# oa_sevenfortyfun.net
KiCad netlist of a schematic drawn in EAGLE
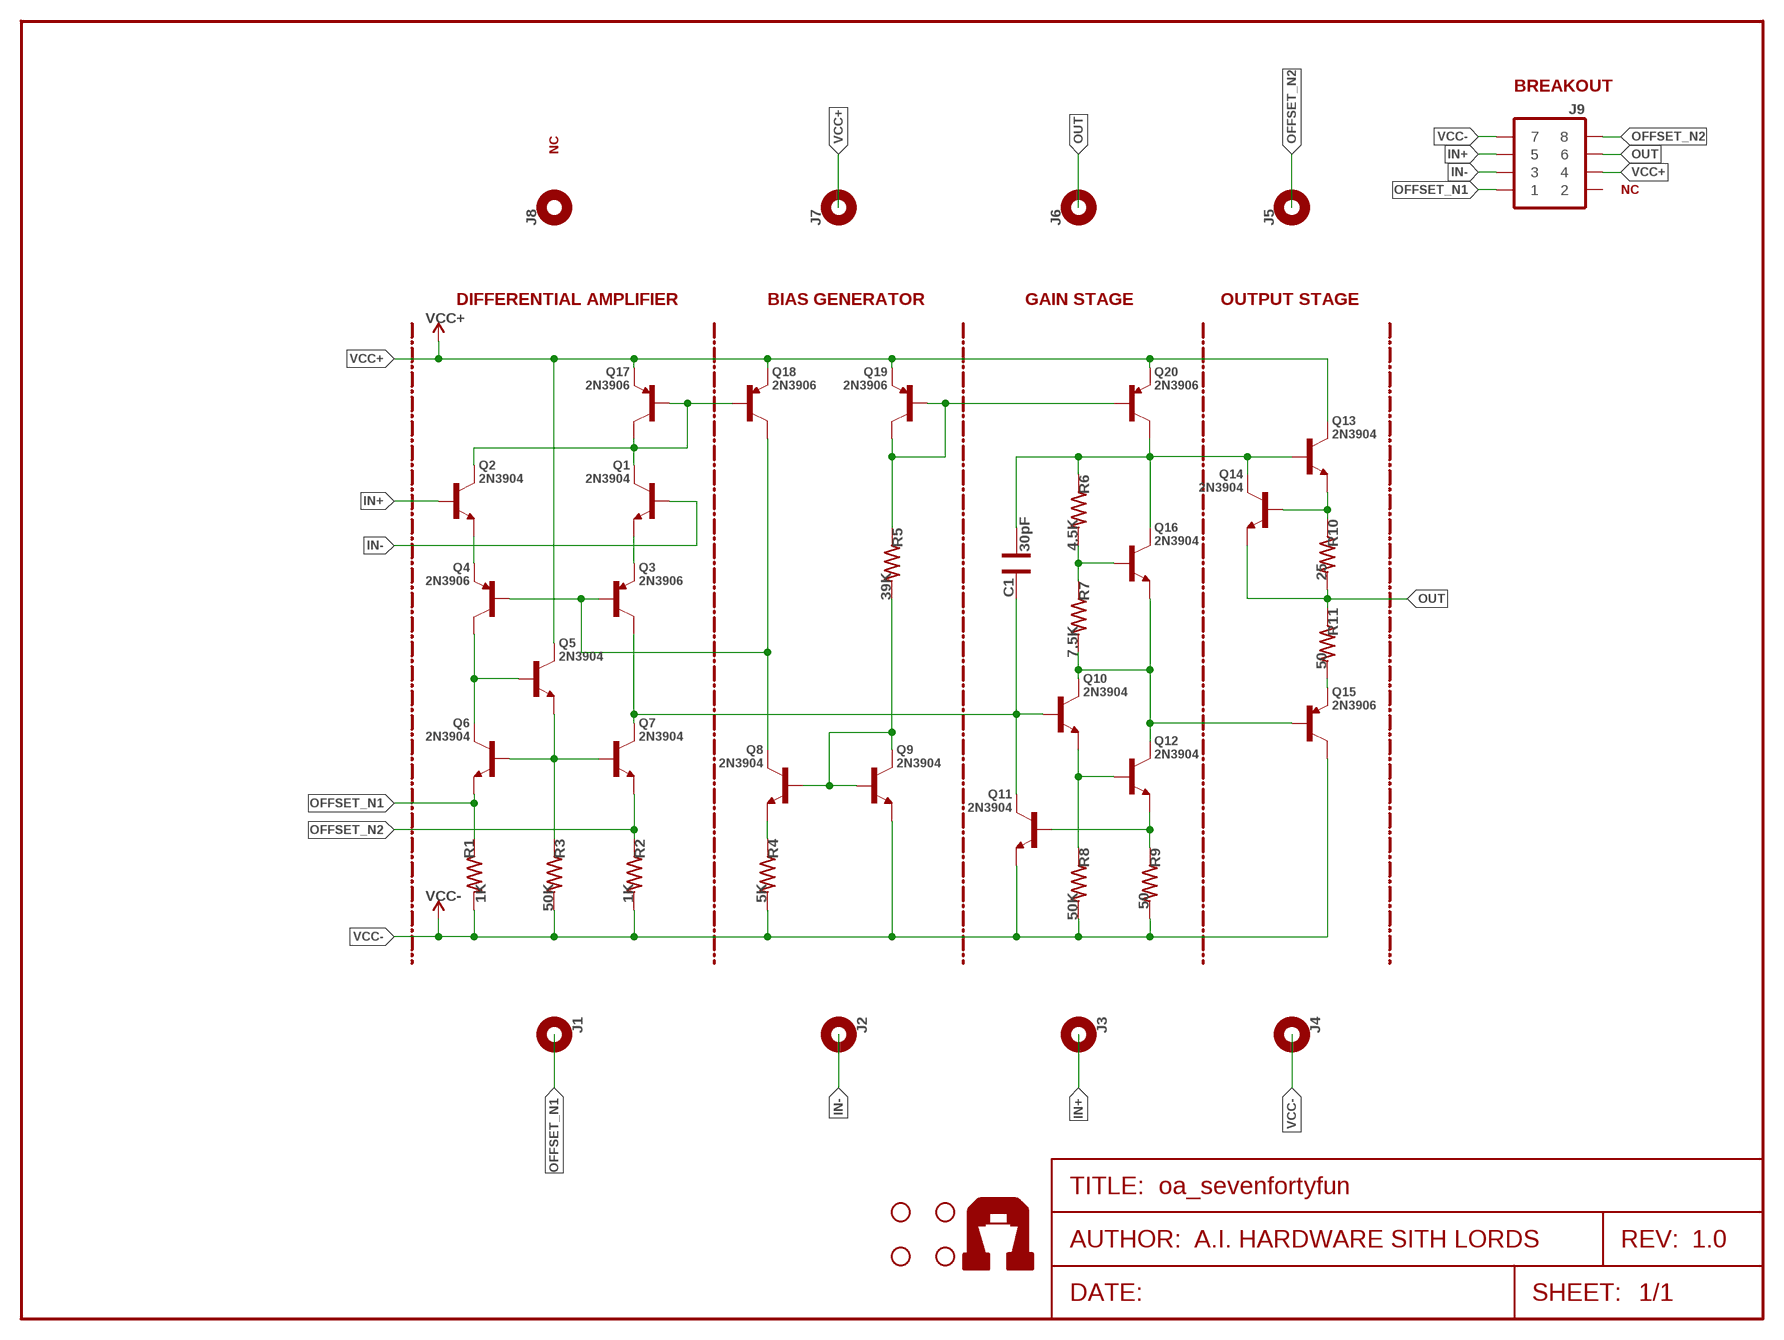
[diagram p0: schematic, sheet 1]

(export (version "E")
  (design (tool "Eeschema 10.0.6"))
  (components
    (comp (ref "C1")
      (value "30pF")
      (footprint "eagle-import:CAP-025X050")
      (libsource (lib "eagle-import") (part "CAP025X050"))
    )
    (comp (ref "J1")
      (value "1X01-TERM")
      (footprint "eagle-import:1X01-TERM")
      (libsource (lib "eagle-import") (part "1X01-TERM"))
    )
    (comp (ref "J2")
      (value "1X01-TERM")
      (footprint "eagle-import:1X01-TERM")
      (libsource (lib "eagle-import") (part "1X01-TERM"))
    )
    (comp (ref "J3")
      (value "1X01-TERM")
      (footprint "eagle-import:1X01-TERM")
      (libsource (lib "eagle-import") (part "1X01-TERM"))
    )
    (comp (ref "J4")
      (value "1X01-TERM")
      (footprint "eagle-import:1X01-TERM")
      (libsource (lib "eagle-import") (part "1X01-TERM"))
    )
    (comp (ref "J5")
      (value "1X01-TERM")
      (footprint "eagle-import:1X01-TERM")
      (libsource (lib "eagle-import") (part "1X01-TERM"))
    )
    (comp (ref "J6")
      (value "1X01-TERM")
      (footprint "eagle-import:1X01-TERM")
      (libsource (lib "eagle-import") (part "1X01-TERM"))
    )
    (comp (ref "J7")
      (value "1X01-TERM")
      (footprint "eagle-import:1X01-TERM")
      (libsource (lib "eagle-import") (part "1X01-TERM"))
    )
    (comp (ref "J8")
      (value "1X01-TERM")
      (footprint "eagle-import:1X01-TERM")
      (libsource (lib "eagle-import") (part "1X01-TERM"))
    )
    (comp (ref "J9")
      (value "2X04SHR")
      (footprint "eagle-import:2X04-SHR")
      (libsource (lib "eagle-import") (part "2X04SHR"))
    )
    (comp (ref "Q1")
      (value "2N3904")
      (footprint "eagle-import:TO-92-NPN")
      (libsource (lib "eagle-import") (part "TRANSISTOR-NPN"))
    )
    (comp (ref "Q2")
      (value "2N3904")
      (footprint "eagle-import:TO-92-NPN")
      (libsource (lib "eagle-import") (part "TRANSISTOR-NPN"))
    )
    (comp (ref "Q3")
      (value "2N3906")
      (footprint "eagle-import:TO-92-PNP")
      (libsource (lib "eagle-import") (part "TRANSISTOR-PNP"))
    )
    (comp (ref "Q4")
      (value "2N3906")
      (footprint "eagle-import:TO-92-PNP")
      (libsource (lib "eagle-import") (part "TRANSISTOR-PNP"))
    )
    (comp (ref "Q5")
      (value "2N3904")
      (footprint "eagle-import:TO-92-NPN")
      (libsource (lib "eagle-import") (part "TRANSISTOR-NPN"))
    )
    (comp (ref "Q6")
      (value "2N3904")
      (footprint "eagle-import:TO-92-NPN")
      (libsource (lib "eagle-import") (part "TRANSISTOR-NPN"))
    )
    (comp (ref "Q7")
      (value "2N3904")
      (footprint "eagle-import:TO-92-NPN")
      (libsource (lib "eagle-import") (part "TRANSISTOR-NPN"))
    )
    (comp (ref "Q8")
      (value "2N3904")
      (footprint "eagle-import:TO-92-NPN")
      (libsource (lib "eagle-import") (part "TRANSISTOR-NPN"))
    )
    (comp (ref "Q9")
      (value "2N3904")
      (footprint "eagle-import:TO-92-NPN")
      (libsource (lib "eagle-import") (part "TRANSISTOR-NPN"))
    )
    (comp (ref "Q10")
      (value "2N3904")
      (footprint "eagle-import:TO-92-NPN")
      (libsource (lib "eagle-import") (part "TRANSISTOR-NPN"))
    )
    (comp (ref "Q11")
      (value "2N3904")
      (footprint "eagle-import:TO-92-NPN")
      (libsource (lib "eagle-import") (part "TRANSISTOR-NPN"))
    )
    (comp (ref "Q12")
      (value "2N3904")
      (footprint "eagle-import:TO-92-NPN")
      (libsource (lib "eagle-import") (part "TRANSISTOR-NPN"))
    )
    (comp (ref "Q13")
      (value "2N3904")
      (footprint "eagle-import:TO-92-NPN")
      (libsource (lib "eagle-import") (part "TRANSISTOR-NPN"))
    )
    (comp (ref "Q14")
      (value "2N3904")
      (footprint "eagle-import:TO-92-NPN")
      (libsource (lib "eagle-import") (part "TRANSISTOR-NPN"))
    )
    (comp (ref "Q15")
      (value "2N3906")
      (footprint "eagle-import:TO-92-PNP")
      (libsource (lib "eagle-import") (part "TRANSISTOR-PNP"))
    )
    (comp (ref "Q16")
      (value "2N3904")
      (footprint "eagle-import:TO-92-NPN")
      (libsource (lib "eagle-import") (part "TRANSISTOR-NPN"))
    )
    (comp (ref "Q17")
      (value "2N3906")
      (footprint "eagle-import:TO-92-PNP")
      (libsource (lib "eagle-import") (part "TRANSISTOR-PNP"))
    )
    (comp (ref "Q18")
      (value "2N3906")
      (footprint "eagle-import:TO-92-PNP")
      (libsource (lib "eagle-import") (part "TRANSISTOR-PNP"))
    )
    (comp (ref "Q19")
      (value "2N3906")
      (footprint "eagle-import:TO-92-PNP")
      (libsource (lib "eagle-import") (part "TRANSISTOR-PNP"))
    )
    (comp (ref "Q20")
      (value "2N3906")
      (footprint "eagle-import:TO-92-PNP")
      (libsource (lib "eagle-import") (part "TRANSISTOR-PNP"))
    )
    (comp (ref "R1")
      (value "1K")
      (footprint "eagle-import:RES-AXIAL-0.4")
      (libsource (lib "eagle-import") (part "RESAXIAL-0.4"))
    )
    (comp (ref "R2")
      (value "1K")
      (footprint "eagle-import:RES-AXIAL-0.4")
      (libsource (lib "eagle-import") (part "RESAXIAL-0.4"))
    )
    (comp (ref "R3")
      (value "50K")
      (footprint "eagle-import:RES-AXIAL-0.4")
      (libsource (lib "eagle-import") (part "RESAXIAL-0.4"))
    )
    (comp (ref "R4")
      (value "5K")
      (footprint "eagle-import:RES-AXIAL-0.4")
      (libsource (lib "eagle-import") (part "RESAXIAL-0.4"))
    )
    (comp (ref "R5")
      (value "39K")
      (footprint "eagle-import:RES-AXIAL-0.4")
      (libsource (lib "eagle-import") (part "RESAXIAL-0.4"))
    )
    (comp (ref "R6")
      (value "4.5K")
      (footprint "eagle-import:RES-AXIAL-0.4")
      (libsource (lib "eagle-import") (part "RESAXIAL-0.4"))
    )
    (comp (ref "R7")
      (value "7.5K")
      (footprint "eagle-import:RES-AXIAL-0.4")
      (libsource (lib "eagle-import") (part "RESAXIAL-0.4"))
    )
    (comp (ref "R8")
      (value "50K")
      (footprint "eagle-import:RES-AXIAL-0.4")
      (libsource (lib "eagle-import") (part "RESAXIAL-0.4"))
    )
    (comp (ref "R9")
      (value "50")
      (footprint "eagle-import:RES-AXIAL-0.4")
      (libsource (lib "eagle-import") (part "RESAXIAL-0.4"))
    )
    (comp (ref "R10")
      (value "25")
      (footprint "eagle-import:RES-AXIAL-0.4")
      (libsource (lib "eagle-import") (part "RESAXIAL-0.4"))
    )
    (comp (ref "R11")
      (value "50")
      (footprint "eagle-import:RES-AXIAL-0.4")
      (libsource (lib "eagle-import") (part "RESAXIAL-0.4"))
    )
    (comp (ref "STANDOFF1")
      (value "STAND-OFF")
      (footprint "eagle-import:STAND-OFF")
      (libsource (lib "eagle-import") (part "STAND-OFF"))
    )
    (comp (ref "STANDOFF2")
      (value "STAND-OFF")
      (footprint "eagle-import:STAND-OFF")
      (libsource (lib "eagle-import") (part "STAND-OFF"))
    )
    (comp (ref "STANDOFF3")
      (value "STAND-OFF")
      (footprint "eagle-import:STAND-OFF")
      (libsource (lib "eagle-import") (part "STAND-OFF"))
    )
    (comp (ref "STANDOFF4")
      (value "STAND-OFF")
      (footprint "eagle-import:STAND-OFF")
      (libsource (lib "eagle-import") (part "STAND-OFF"))
    )
    (comp (ref "U$3")
      (value "AI-LOGOL")
      (footprint "eagle-import:AI-LOGO-L")
      (libsource (lib "eagle-import") (part "AI-LOGOL"))
    )
  )
  (nets
    (net (code "1") (name "IN+") (class "Default")
      (node (ref "J3") (pin "1") (pinfunction "1_1") (pintype "bidirectional"))
      (node (ref "J9") (pin "5") (pinfunction "5_5") (pintype "bidirectional"))
      (node (ref "Q2") (pin "2") (pinfunction "B_2") (pintype "passive"))
    )
    (net (code "2") (name "IN-") (class "Default")
      (node (ref "J2") (pin "1") (pinfunction "1_1") (pintype "bidirectional"))
      (node (ref "J9") (pin "3") (pinfunction "3_3") (pintype "bidirectional"))
      (node (ref "Q1") (pin "2") (pinfunction "B_2") (pintype "passive"))
    )
    (net (code "3") (name "Net-(Q1-C)") (class "Default")
      (node (ref "Q1") (pin "3") (pinfunction "C_3") (pintype "passive"))
      (node (ref "Q17") (pin "1") (pinfunction "C_1") (pintype "passive"))
      (node (ref "Q17") (pin "2") (pinfunction "B_2") (pintype "passive"))
      (node (ref "Q18") (pin "2") (pinfunction "B_2") (pintype "passive"))
      (node (ref "Q2") (pin "3") (pinfunction "C_3") (pintype "passive"))
    )
    (net (code "4") (name "Net-(Q1-E)") (class "Default")
      (node (ref "Q1") (pin "1") (pinfunction "E_1") (pintype "passive"))
      (node (ref "Q3") (pin "3") (pinfunction "E_3") (pintype "passive"))
    )
    (net (code "5") (name "Net-(Q2-E)") (class "Default")
      (node (ref "Q2") (pin "1") (pinfunction "E_1") (pintype "passive"))
      (node (ref "Q4") (pin "3") (pinfunction "E_3") (pintype "passive"))
    )
    (net (code "6") (name "Net-(Q4-C)") (class "Default")
      (node (ref "Q4") (pin "1") (pinfunction "C_1") (pintype "passive"))
      (node (ref "Q5") (pin "2") (pinfunction "B_2") (pintype "passive"))
      (node (ref "Q6") (pin "3") (pinfunction "C_3") (pintype "passive"))
    )
    (net (code "7") (name "Net-(Q5-E)") (class "Default")
      (node (ref "Q5") (pin "1") (pinfunction "E_1") (pintype "passive"))
      (node (ref "Q6") (pin "2") (pinfunction "B_2") (pintype "passive"))
      (node (ref "Q7") (pin "2") (pinfunction "B_2") (pintype "passive"))
      (node (ref "R3") (pin "P$1") (pinfunction "1_P$1") (pintype "passive"))
    )
    (net (code "8") (name "Net-(Q8-B)") (class "Default")
      (node (ref "Q8") (pin "2") (pinfunction "B_2") (pintype "passive"))
      (node (ref "Q9") (pin "2") (pinfunction "B_2") (pintype "passive"))
      (node (ref "Q9") (pin "3") (pinfunction "C_3") (pintype "passive"))
      (node (ref "R5") (pin "P$2") (pinfunction "2_P$2") (pintype "passive"))
    )
    (net (code "9") (name "Net-(Q8-E)") (class "Default")
      (node (ref "Q8") (pin "1") (pinfunction "E_1") (pintype "passive"))
      (node (ref "R4") (pin "P$1") (pinfunction "1_P$1") (pintype "passive"))
    )
    (net (code "10") (name "Net-(Q10-B)") (class "Default")
      (node (ref "C1") (pin "2") (pinfunction "2_2") (pintype "passive"))
      (node (ref "Q10") (pin "2") (pinfunction "B_2") (pintype "passive"))
      (node (ref "Q11") (pin "3") (pinfunction "C_3") (pintype "passive"))
      (node (ref "Q3") (pin "1") (pinfunction "C_1") (pintype "passive"))
      (node (ref "Q7") (pin "3") (pinfunction "C_3") (pintype "passive"))
    )
    (net (code "11") (name "Net-(Q10-C)") (class "Default")
      (node (ref "Q10") (pin "3") (pinfunction "C_3") (pintype "passive"))
      (node (ref "Q12") (pin "3") (pinfunction "C_3") (pintype "passive"))
      (node (ref "Q15") (pin "2") (pinfunction "B_2") (pintype "passive"))
      (node (ref "Q16") (pin "1") (pinfunction "E_1") (pintype "passive"))
      (node (ref "R7") (pin "P$2") (pinfunction "2_P$2") (pintype "passive"))
    )
    (net (code "12") (name "Net-(Q10-E)") (class "Default")
      (node (ref "Q10") (pin "1") (pinfunction "E_1") (pintype "passive"))
      (node (ref "Q12") (pin "2") (pinfunction "B_2") (pintype "passive"))
      (node (ref "R8") (pin "P$1") (pinfunction "1_P$1") (pintype "passive"))
    )
    (net (code "13") (name "Net-(Q11-B)") (class "Default")
      (node (ref "Q11") (pin "2") (pinfunction "B_2") (pintype "passive"))
      (node (ref "Q12") (pin "1") (pinfunction "E_1") (pintype "passive"))
      (node (ref "R9") (pin "P$1") (pinfunction "1_P$1") (pintype "passive"))
    )
    (net (code "14") (name "Net-(Q13-B)") (class "Default")
      (node (ref "C1") (pin "1") (pinfunction "1_1") (pintype "passive"))
      (node (ref "Q13") (pin "2") (pinfunction "B_2") (pintype "passive"))
      (node (ref "Q14") (pin "3") (pinfunction "C_3") (pintype "passive"))
      (node (ref "Q16") (pin "3") (pinfunction "C_3") (pintype "passive"))
      (node (ref "Q20") (pin "1") (pinfunction "C_1") (pintype "passive"))
      (node (ref "R6") (pin "P$1") (pinfunction "1_P$1") (pintype "passive"))
    )
    (net (code "15") (name "Net-(Q13-E)") (class "Default")
      (node (ref "Q13") (pin "1") (pinfunction "E_1") (pintype "passive"))
      (node (ref "Q14") (pin "2") (pinfunction "B_2") (pintype "passive"))
      (node (ref "R10") (pin "P$1") (pinfunction "1_P$1") (pintype "passive"))
    )
    (net (code "16") (name "Net-(Q15-E)") (class "Default")
      (node (ref "Q15") (pin "3") (pinfunction "E_3") (pintype "passive"))
      (node (ref "R11") (pin "P$2") (pinfunction "2_P$2") (pintype "passive"))
    )
    (net (code "17") (name "Net-(Q16-B)") (class "Default")
      (node (ref "Q16") (pin "2") (pinfunction "B_2") (pintype "passive"))
      (node (ref "R6") (pin "P$2") (pinfunction "2_P$2") (pintype "passive"))
      (node (ref "R7") (pin "P$1") (pinfunction "1_P$1") (pintype "passive"))
    )
    (net (code "18") (name "Net-(Q18-C)") (class "Default")
      (node (ref "Q18") (pin "1") (pinfunction "C_1") (pintype "passive"))
      (node (ref "Q3") (pin "2") (pinfunction "B_2") (pintype "passive"))
      (node (ref "Q4") (pin "2") (pinfunction "B_2") (pintype "passive"))
      (node (ref "Q8") (pin "3") (pinfunction "C_3") (pintype "passive"))
    )
    (net (code "19") (name "Net-(Q19-B)") (class "Default")
      (node (ref "Q19") (pin "1") (pinfunction "C_1") (pintype "passive"))
      (node (ref "Q19") (pin "2") (pinfunction "B_2") (pintype "passive"))
      (node (ref "Q20") (pin "2") (pinfunction "B_2") (pintype "passive"))
      (node (ref "R5") (pin "P$1") (pinfunction "1_P$1") (pintype "passive"))
    )
    (net (code "20") (name "OFFSET_N1") (class "Default")
      (node (ref "J1") (pin "1") (pinfunction "1_1") (pintype "bidirectional"))
      (node (ref "J9") (pin "1") (pinfunction "1_1") (pintype "bidirectional"))
      (node (ref "Q6") (pin "1") (pinfunction "E_1") (pintype "passive"))
      (node (ref "R1") (pin "P$1") (pinfunction "1_P$1") (pintype "passive"))
    )
    (net (code "21") (name "OFFSET_N2") (class "Default")
      (node (ref "J5") (pin "1") (pinfunction "1_1") (pintype "bidirectional"))
      (node (ref "J9") (pin "8") (pinfunction "8_8") (pintype "bidirectional"))
      (node (ref "Q7") (pin "1") (pinfunction "E_1") (pintype "passive"))
      (node (ref "R2") (pin "P$1") (pinfunction "1_P$1") (pintype "passive"))
    )
    (net (code "22") (name "OUT") (class "Default")
      (node (ref "J6") (pin "1") (pinfunction "1_1") (pintype "bidirectional"))
      (node (ref "J9") (pin "6") (pinfunction "6_6") (pintype "bidirectional"))
      (node (ref "Q14") (pin "1") (pinfunction "E_1") (pintype "passive"))
      (node (ref "R10") (pin "P$2") (pinfunction "2_P$2") (pintype "passive"))
      (node (ref "R11") (pin "P$1") (pinfunction "1_P$1") (pintype "passive"))
    )
    (net (code "23") (name "VCC+") (class "Default")
      (node (ref "J7") (pin "1") (pinfunction "1_1") (pintype "bidirectional"))
      (node (ref "J9") (pin "4") (pinfunction "4_4") (pintype "bidirectional"))
      (node (ref "Q13") (pin "3") (pinfunction "C_3") (pintype "passive"))
      (node (ref "Q17") (pin "3") (pinfunction "E_3") (pintype "passive"))
      (node (ref "Q18") (pin "3") (pinfunction "E_3") (pintype "passive"))
      (node (ref "Q19") (pin "3") (pinfunction "E_3") (pintype "passive"))
      (node (ref "Q20") (pin "3") (pinfunction "E_3") (pintype "passive"))
      (node (ref "Q5") (pin "3") (pinfunction "C_3") (pintype "passive"))
    )
    (net (code "24") (name "VCC-") (class "Default")
      (node (ref "J4") (pin "1") (pinfunction "1_1") (pintype "bidirectional"))
      (node (ref "J9") (pin "7") (pinfunction "7_7") (pintype "bidirectional"))
      (node (ref "Q11") (pin "1") (pinfunction "E_1") (pintype "passive"))
      (node (ref "Q15") (pin "1") (pinfunction "C_1") (pintype "passive"))
      (node (ref "Q9") (pin "1") (pinfunction "E_1") (pintype "passive"))
      (node (ref "R1") (pin "P$2") (pinfunction "2_P$2") (pintype "passive"))
      (node (ref "R2") (pin "P$2") (pinfunction "2_P$2") (pintype "passive"))
      (node (ref "R3") (pin "P$2") (pinfunction "2_P$2") (pintype "passive"))
      (node (ref "R4") (pin "P$2") (pinfunction "2_P$2") (pintype "passive"))
      (node (ref "R8") (pin "P$2") (pinfunction "2_P$2") (pintype "passive"))
      (node (ref "R9") (pin "P$2") (pinfunction "2_P$2") (pintype "passive"))
    )
    (net (code "25") (name "unconnected-(J8-Pad1)") (class "Default")
      (node (ref "J8") (pin "1") (pinfunction "1_1") (pintype "bidirectional"))
    )
    (net (code "26") (name "unconnected-(J9-Pad2)") (class "Default")
      (node (ref "J9") (pin "2") (pinfunction "2_2") (pintype "bidirectional"))
    )
  )
)
